# RF_Transmit.net
KiCad netlist of a schematic drawn in Altium Designer
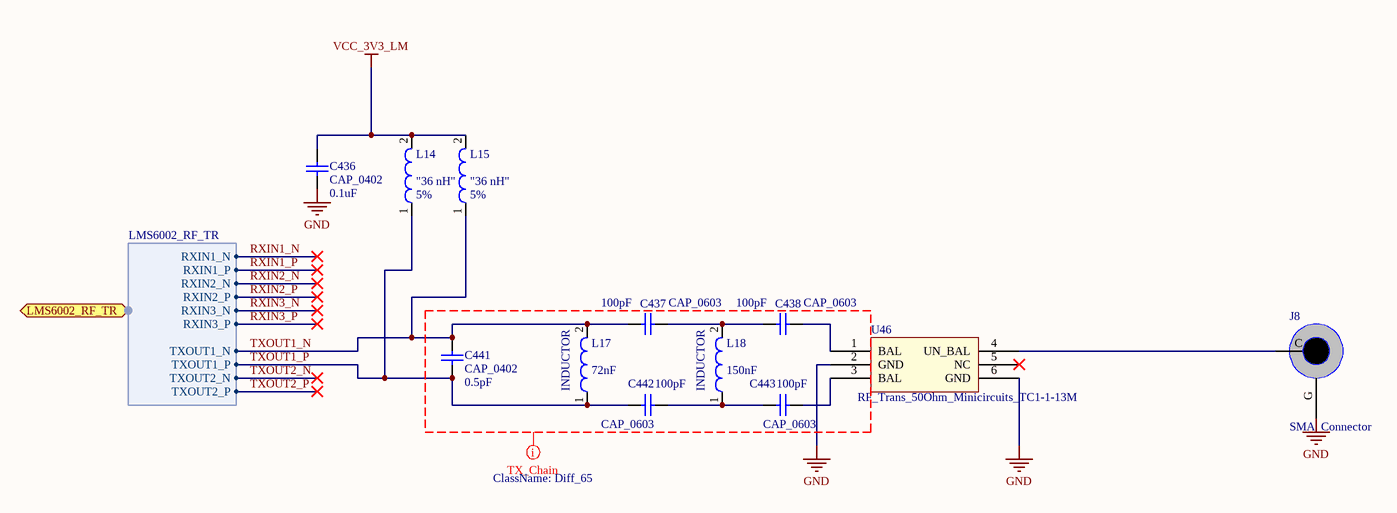
[diagram p0: RF_Transmit.SchDoc]

(export (version "E")
  (design (tool "Eeschema 10.0.6"))
  (components
    (comp (ref "C436")
      (value "CAP_0402")
      (footprint "CAPC0402(1005)60_N")
      (description "0.1uf, ceramic, 10%, 6.3V, X5R, 0402")
      (fields
        (field (name "ALTIUM_VALUE") "0.1uF")
        (field (name "TOLERANCE") "10%")
        (field (name "PART NUMBER") "C1005X5R0J104K")
      )
      (libsource (lib "COMRAD_Database") (part "CAP_0402"))
    )
    (comp (ref "C437")
      (value "CAP_0603")
      (footprint "CAPC0603(1608)100_N")
      (description "CAP CER 100PF 200V 5% NP0 0603")
      (fields
        (field (name "ALTIUM_VALUE") "100pF")
        (field (name "TOLERANCE") "5%")
        (field (name "PART NUMBER") "VJ0603D101JXCAJ")
      )
      (libsource (lib "COMRAD_Database") (part "CAP_0603"))
    )
    (comp (ref "C438")
      (value "CAP_0603")
      (footprint "CAPC0603(1608)100_N")
      (description "CAP CER 100PF 200V 5% NP0 0603")
      (fields
        (field (name "ALTIUM_VALUE") "100pF")
        (field (name "TOLERANCE") "5%")
        (field (name "PART NUMBER") "VJ0603D101JXCAJ")
      )
      (libsource (lib "COMRAD_Database") (part "CAP_0603"))
    )
    (comp (ref "C441")
      (value "CAP_0402")
      (footprint "CAPC0402(1005)60_N")
      (description "CAP CER 0.5PF 25V NP0 0402")
      (fields
        (field (name "ALTIUM_VALUE") "0.5pF")
        (field (name "PART NUMBER") "C0402C508D3GACTU")
        (field (name "MANUFACTURER") "Kemet")
      )
      (libsource (lib "COMRAD_Database") (part "CAP_0402"))
    )
    (comp (ref "C442")
      (value "CAP_0603")
      (footprint "CAPC0603(1608)100_N")
      (description "CAP CER 100PF 200V 5% NP0 0603")
      (fields
        (field (name "ALTIUM_VALUE") "100pF")
        (field (name "TOLERANCE") "5%")
        (field (name "PART NUMBER") "VJ0603D101JXCAJ")
      )
      (libsource (lib "COMRAD_Database") (part "CAP_0603"))
    )
    (comp (ref "C443")
      (value "CAP_0603")
      (footprint "CAPC0603(1608)100_N")
      (description "CAP CER 100PF 200V 5% NP0 0603")
      (fields
        (field (name "ALTIUM_VALUE") "100pF")
        (field (name "TOLERANCE") "5%")
        (field (name "PART NUMBER") "VJ0603D101JXCAJ")
      )
      (libsource (lib "COMRAD_Database") (part "CAP_0603"))
    )
    (comp (ref "J8")
      (value "SMA_Connector")
      (footprint "Connector_SMA_Amphenol_132255_Edgemount")
      (description "CONN RCPT SMA END LAUNCH PCB")
      (fields (field (name "PART NUMBER") "132255") (field (name "MANUFACTURER") "Amphenol Connex"))
      (libsource (lib "COMRAD_Database") (part "SMA_Connector"))
    )
    (comp (ref "L14")
      (value "\"36 nH\"")
      (footprint "Inductor0402(1005)")
      (description "Inductor 36 nH 0402 5%")
      (fields
        (field (name "TOLERANCE") "5%")
        (field (name "PART NUMBER") "\"0402CS-36NX_L\"")
        (field (name "MANUFACTURER") "Coilcraft")
      )
      (libsource (lib "COMRAD_Database") (part "SYM-0029-00001-1"))
    )
    (comp (ref "L15")
      (value "\"36 nH\"")
      (footprint "Inductor0402(1005)")
      (description "Inductor 36 nH 0402 5%")
      (fields
        (field (name "TOLERANCE") "5%")
        (field (name "PART NUMBER") "\"0402CS-36NX_L\"")
        (field (name "MANUFACTURER") "Coilcraft")
      )
      (libsource (lib "COMRAD_Database") (part "SYM-0029-00001-1"))
    )
    (comp (ref "L17")
      (value "INDUCTOR")
      (footprint "Inductor0603(1608)")
      (description "INDUCTOR, 72nF, 2%, 1.4A, 0603")
      (fields
        (field (name "ALTIUM_VALUE") "72nF")
        (field (name "TOLERANCE") "2%")
        (field (name "PART NUMBER") "0603LS-72NXGLB")
      )
      (libsource (lib "COMRAD_Database") (part "SYM-0029-00001-1"))
    )
    (comp (ref "L18")
      (value "INDUCTOR")
      (footprint "Inductor0603(1608)")
      (description "INDUCTOR, 150nF, 2%, 1.4A, 0603")
      (fields
        (field (name "ALTIUM_VALUE") "150nF")
        (field (name "TOLERANCE") "2%")
        (field (name "PART NUMBER") "0603LS-151XGLB")
      )
      (libsource (lib "COMRAD_Database") (part "INDUCTOR"))
    )
    (comp (ref "U46")
      (value "RF_Trans_50Ohm_Minicircuits_TC1-1-13M")
      (footprint "RF_Trans_50Ohm_Minicircuits_TC1-1-13M_AT224")
      (description "RF Transformer, 50 Ohm, 4.5 to 3000 MHz, Leadless Surface Mount, AT224")
      (fields (field (name "PART NUMBER") "TC1-1-13M") (field (name "MANUFACTURER") "Minicircuits"))
      (libsource (lib "COMRAD_Database") (part "RF_Trans_50Ohm_Minicircuits_TC1-1-13M"))
    )
  )
  (nets
    (net (code "8") (name "/TXOUT1_N") (class "Default")
      (node (ref "C437") (pin "1") (pinfunction "1_1") (pintype "passive"))
      (node (ref "C441") (pin "2") (pinfunction "2_2") (pintype "passive"))
      (node (ref "L15") (pin "1") (pinfunction "1_1") (pintype "passive"))
      (node (ref "L17") (pin "2") (pinfunction "2_2") (pintype "passive"))
    )
    (net (code "9") (name "/TXOUT1_P") (class "Default")
      (node (ref "C441") (pin "1") (pinfunction "1_1") (pintype "passive"))
      (node (ref "C442") (pin "1") (pinfunction "1_1") (pintype "passive"))
      (node (ref "L14") (pin "1") (pinfunction "1_1") (pintype "passive"))
      (node (ref "L17") (pin "1") (pinfunction "1_1") (pintype "passive"))
    )
    (net (code "13") (name "GND") (class "Default")
      (node (ref "C436") (pin "1") (pinfunction "1_1") (pintype "passive"))
      (node (ref "J8") (pin "G") (pinfunction "2_G") (pintype "passive"))
      (node (ref "U46") (pin "2") (pinfunction "GND_2") (pintype "passive"))
      (node (ref "U46") (pin "6") (pinfunction "GND_6") (pintype "passive"))
    )
    (net (code "14") (name "Net-(C437-Pad2)") (class "Default")
      (node (ref "C437") (pin "2") (pinfunction "2_2") (pintype "passive"))
      (node (ref "C438") (pin "1") (pinfunction "1_1") (pintype "passive"))
      (node (ref "L18") (pin "2") (pinfunction "2_2") (pintype "passive"))
    )
    (net (code "15") (name "Net-(C438-Pad2)") (class "Default")
      (node (ref "C438") (pin "2") (pinfunction "2_2") (pintype "passive"))
      (node (ref "U46") (pin "1") (pinfunction "BAL_1") (pintype "passive"))
    )
    (net (code "16") (name "Net-(C442-Pad2)") (class "Default")
      (node (ref "C442") (pin "2") (pinfunction "2_2") (pintype "passive"))
      (node (ref "C443") (pin "1") (pinfunction "1_1") (pintype "passive"))
      (node (ref "L18") (pin "1") (pinfunction "1_1") (pintype "passive"))
    )
    (net (code "17") (name "Net-(C443-Pad2)") (class "Default")
      (node (ref "C443") (pin "2") (pinfunction "2_2") (pintype "passive"))
      (node (ref "U46") (pin "3") (pinfunction "BAL_3") (pintype "passive"))
    )
    (net (code "18") (name "Net-(J8-1)") (class "Default")
      (node (ref "J8") (pin "C") (pinfunction "1_C") (pintype "passive"))
      (node (ref "U46") (pin "4") (pinfunction "UN_BAL_4") (pintype "passive"))
    )
    (net (code "19") (name "VCC_3V3_LM") (class "Default")
      (node (ref "C436") (pin "2") (pinfunction "2_2") (pintype "passive"))
      (node (ref "L14") (pin "2") (pinfunction "2_2") (pintype "passive"))
      (node (ref "L15") (pin "2") (pinfunction "2_2") (pintype "passive"))
    )
    (net (code "20") (name "unconnected-(U46-NC-Pad5)") (class "Default")
      (node (ref "U46") (pin "5") (pinfunction "NC_5") (pintype "passive+no_connect"))
    )
  )
)
